# MA-Portenta.net
KiCad netlist of a schematic drawn in Altium Designer
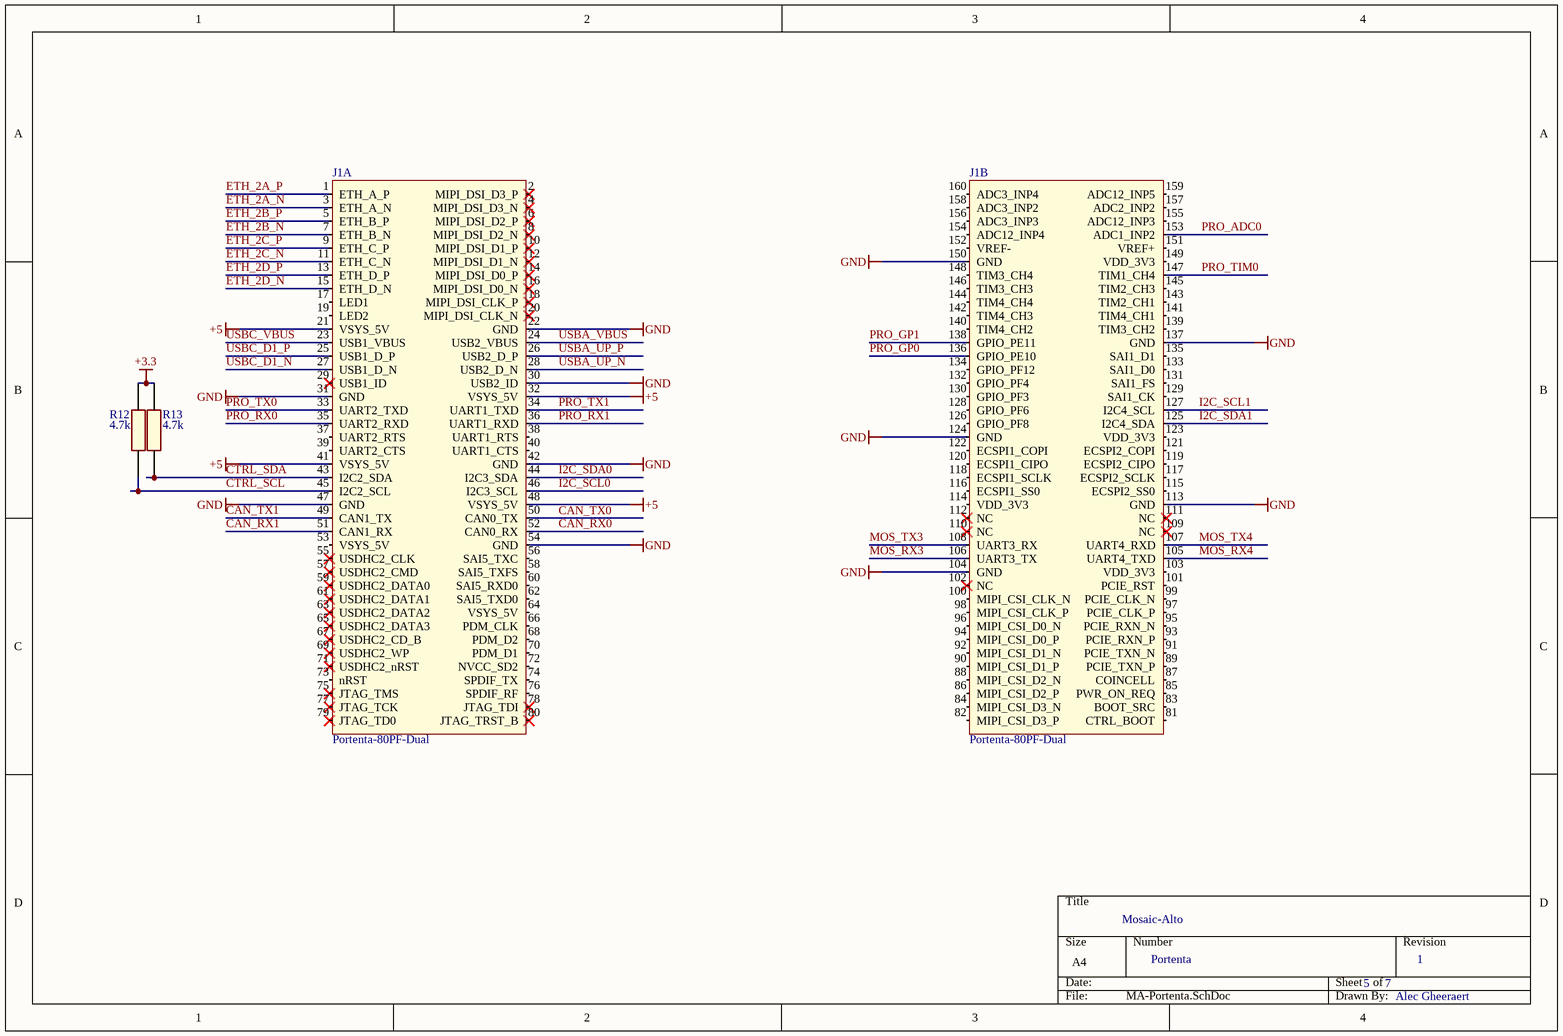
[diagram p0: MA-Portenta.SchDoc]

(export (version "E")
  (design (tool "Eeschema 10.0.6"))
  (components
    (comp (ref "J1")
      (value "Portenta-80PF-Dual")
      (footprint "HRS_DF40C-80DP-0.4V(51)")
      (description "80 Pin Arduino Pro Female")
      (fields (field (name "MANUFACTURER") "Arduino"))
      (libsource (lib "Ghrt") (part "Portenta-80P-Dual"))
    )
    (comp (ref "R12")
      (value "4.7k")
      (footprint "RESC1005X40N")
      (description "0402I 4.7k")
      (fields (field (name "MANUFACTURER") "Walsin") (field (name "TOLERANCE") "1%"))
      (libsource (lib "Ghrt") (part "WR04X4701FTL"))
    )
    (comp (ref "R13")
      (value "4.7k")
      (footprint "RESC1005X40N")
      (description "0402I 4.7k")
      (fields (field (name "MANUFACTURER") "Walsin") (field (name "TOLERANCE") "1%"))
      (libsource (lib "") (part "WR04X4701FTL_1"))
    )
  )
  (nets
    (net (code "1") (name "+3.3") (class "Default")
      (node (ref "R12") (pin "2") (pinfunction "2_2") (pintype "passive"))
      (node (ref "R13") (pin "1") (pinfunction "1_1") (pintype "passive"))
    )
    (net (code "2") (name "+5") (class "Default")
      (node (ref "J1") (pin "21") (pinfunction "VSYS_5V_21") (pintype "passive"))
      (node (ref "J1") (pin "32") (pinfunction "VSYS_5V_32") (pintype "passive"))
      (node (ref "J1") (pin "41") (pinfunction "VSYS_5V_41") (pintype "passive"))
      (node (ref "J1") (pin "48") (pinfunction "VSYS_5V_48") (pintype "passive"))
    )
    (net (code "3") (name "/CAN_RX0") (class "Default")
      (node (ref "J1") (pin "52") (pinfunction "CAN0_RX_52") (pintype "passive"))
    )
    (net (code "4") (name "/CAN_RX1") (class "Default")
      (node (ref "J1") (pin "51") (pinfunction "CAN1_RX_51") (pintype "passive"))
    )
    (net (code "5") (name "/CAN_TX0") (class "Default")
      (node (ref "J1") (pin "50") (pinfunction "CAN0_TX_50") (pintype "passive"))
    )
    (net (code "6") (name "/CAN_TX1") (class "Default")
      (node (ref "J1") (pin "49") (pinfunction "CAN1_TX_49") (pintype "passive"))
    )
    (net (code "7") (name "/CTRL_SCL") (class "Default")
      (node (ref "J1") (pin "45") (pinfunction "I2C2_SCL_45") (pintype "passive"))
      (node (ref "R12") (pin "1") (pinfunction "1_1") (pintype "passive"))
    )
    (net (code "8") (name "/CTRL_SDA") (class "Default")
      (node (ref "J1") (pin "43") (pinfunction "I2C2_SDA_43") (pintype "passive"))
      (node (ref "R13") (pin "2") (pinfunction "2_2") (pintype "passive"))
    )
    (net (code "9") (name "/ETH_2A_N") (class "Default")
      (node (ref "J1") (pin "3") (pinfunction "ETH_A_N_3") (pintype "passive"))
    )
    (net (code "10") (name "/ETH_2A_P") (class "Default")
      (node (ref "J1") (pin "1") (pinfunction "ETH_A_P_1") (pintype "passive"))
    )
    (net (code "11") (name "/ETH_2B_N") (class "Default")
      (node (ref "J1") (pin "7") (pinfunction "ETH_B_N_7") (pintype "passive"))
    )
    (net (code "12") (name "/ETH_2B_P") (class "Default")
      (node (ref "J1") (pin "5") (pinfunction "ETH_B_P_5") (pintype "passive"))
    )
    (net (code "13") (name "/ETH_2C_N") (class "Default")
      (node (ref "J1") (pin "11") (pinfunction "ETH_C_N_11") (pintype "passive"))
    )
    (net (code "14") (name "/ETH_2C_P") (class "Default")
      (node (ref "J1") (pin "9") (pinfunction "ETH_C_P_9") (pintype "passive"))
    )
    (net (code "15") (name "/ETH_2D_N") (class "Default")
      (node (ref "J1") (pin "15") (pinfunction "ETH_D_N_15") (pintype "passive"))
    )
    (net (code "16") (name "/ETH_2D_P") (class "Default")
      (node (ref "J1") (pin "13") (pinfunction "ETH_D_P_13") (pintype "passive"))
    )
    (net (code "17") (name "/I2C_SCL0") (class "Default")
      (node (ref "J1") (pin "46") (pinfunction "I2C3_SCL_46") (pintype "passive"))
    )
    (net (code "18") (name "/I2C_SCL1") (class "Default")
      (node (ref "J1") (pin "127") (pinfunction "I2C4_SCL_127") (pintype "passive"))
    )
    (net (code "19") (name "/I2C_SDA0") (class "Default")
      (node (ref "J1") (pin "44") (pinfunction "I2C3_SDA_44") (pintype "passive"))
    )
    (net (code "20") (name "/I2C_SDA1") (class "Default")
      (node (ref "J1") (pin "125") (pinfunction "I2C4_SDA_125") (pintype "passive"))
    )
    (net (code "21") (name "/MOS_RX3") (class "Default")
      (node (ref "J1") (pin "106") (pinfunction "UART3_TX_106") (pintype "passive"))
    )
    (net (code "22") (name "/MOS_RX4") (class "Default")
      (node (ref "J1") (pin "105") (pinfunction "UART4_TXD_105") (pintype "passive"))
    )
    (net (code "23") (name "/MOS_TX3") (class "Default")
      (node (ref "J1") (pin "108") (pinfunction "UART3_RX_108") (pintype "passive"))
    )
    (net (code "24") (name "/MOS_TX4") (class "Default")
      (node (ref "J1") (pin "107") (pinfunction "UART4_RXD_107") (pintype "passive"))
    )
    (net (code "25") (name "/PRO_ADC0") (class "Default")
      (node (ref "J1") (pin "153") (pinfunction "ADC1_INP2_153") (pintype "passive"))
    )
    (net (code "26") (name "/PRO_GP0") (class "Default")
      (node (ref "J1") (pin "136") (pinfunction "GPIO_PE10_136") (pintype "passive"))
    )
    (net (code "27") (name "/PRO_GP1") (class "Default")
      (node (ref "J1") (pin "138") (pinfunction "GPIO_PE11_138") (pintype "passive"))
    )
    (net (code "28") (name "/PRO_RX0") (class "Default")
      (node (ref "J1") (pin "35") (pinfunction "UART2_RXD_35") (pintype "passive"))
    )
    (net (code "29") (name "/PRO_RX1") (class "Default")
      (node (ref "J1") (pin "36") (pinfunction "UART1_RXD_36") (pintype "passive"))
    )
    (net (code "30") (name "/PRO_TIM0") (class "Default")
      (node (ref "J1") (pin "147") (pinfunction "TIM1_CH4_147") (pintype "passive"))
    )
    (net (code "31") (name "/PRO_TX0") (class "Default")
      (node (ref "J1") (pin "33") (pinfunction "UART2_TXD_33") (pintype "passive"))
    )
    (net (code "32") (name "/PRO_TX1") (class "Default")
      (node (ref "J1") (pin "34") (pinfunction "UART1_TXD_34") (pintype "passive"))
    )
    (net (code "33") (name "/USBA_UP_N") (class "Default")
      (node (ref "J1") (pin "28") (pinfunction "USB2_D_N_28") (pintype "passive"))
    )
    (net (code "34") (name "/USBA_UP_P") (class "Default")
      (node (ref "J1") (pin "26") (pinfunction "USB2_D_P_26") (pintype "passive"))
    )
    (net (code "35") (name "/USBA_VBUS") (class "Default")
      (node (ref "J1") (pin "24") (pinfunction "USB2_VBUS_24") (pintype "passive"))
    )
    (net (code "36") (name "/USBC_D1_N") (class "Default")
      (node (ref "J1") (pin "27") (pinfunction "USB1_D_N_27") (pintype "passive"))
    )
    (net (code "37") (name "/USBC_D1_P") (class "Default")
      (node (ref "J1") (pin "25") (pinfunction "USB1_D_P_25") (pintype "passive"))
    )
    (net (code "38") (name "/USBC_VBUS") (class "Default")
      (node (ref "J1") (pin "23") (pinfunction "USB1_VBUS_23") (pintype "passive"))
    )
    (net (code "39") (name "GND") (class "Default")
      (node (ref "J1") (pin "104") (pinfunction "GND_104") (pintype "passive"))
      (node (ref "J1") (pin "113") (pinfunction "GND_113") (pintype "passive"))
      (node (ref "J1") (pin "124") (pinfunction "GND_124") (pintype "passive"))
      (node (ref "J1") (pin "137") (pinfunction "GND_137") (pintype "passive"))
      (node (ref "J1") (pin "150") (pinfunction "GND_150") (pintype "passive"))
      (node (ref "J1") (pin "22") (pinfunction "GND_22") (pintype "passive"))
      (node (ref "J1") (pin "30") (pinfunction "USB2_ID_30") (pintype "passive"))
      (node (ref "J1") (pin "31") (pinfunction "GND_31") (pintype "passive"))
      (node (ref "J1") (pin "42") (pinfunction "GND_42") (pintype "passive"))
      (node (ref "J1") (pin "47") (pinfunction "GND_47") (pintype "passive"))
      (node (ref "J1") (pin "54") (pinfunction "GND_54") (pintype "passive"))
    )
    (net (code "40") (name "unconnected-(J1A-JTAG_TCK-Pad77)") (class "Default")
      (node (ref "J1") (pin "77") (pinfunction "JTAG_TCK_77") (pintype "passive+no_connect"))
    )
    (net (code "41") (name "unconnected-(J1A-JTAG_TD0-Pad79)") (class "Default")
      (node (ref "J1") (pin "79") (pinfunction "JTAG_TD0_79") (pintype "passive+no_connect"))
    )
    (net (code "42") (name "unconnected-(J1A-JTAG_TDI-Pad78)") (class "Default")
      (node (ref "J1") (pin "78") (pinfunction "JTAG_TDI_78") (pintype "passive+no_connect"))
    )
    (net (code "43") (name "unconnected-(J1A-JTAG_TMS-Pad75)") (class "Default")
      (node (ref "J1") (pin "75") (pinfunction "JTAG_TMS_75") (pintype "passive+no_connect"))
    )
    (net (code "44") (name "unconnected-(J1A-JTAG_TRST_B-Pad80)") (class "Default")
      (node (ref "J1") (pin "80") (pinfunction "JTAG_TRST_B_80") (pintype "passive+no_connect"))
    )
    (net (code "45") (name "unconnected-(J1A-LED1-Pad17)") (class "Default")
      (node (ref "J1") (pin "17") (pinfunction "LED1_17") (pintype "passive"))
    )
    (net (code "46") (name "unconnected-(J1A-LED2-Pad19)") (class "Default")
      (node (ref "J1") (pin "19") (pinfunction "LED2_19") (pintype "passive"))
    )
    (net (code "47") (name "unconnected-(J1A-MIPI_DSI_CLK_N-Pad20)") (class "Default")
      (node (ref "J1") (pin "20") (pinfunction "MIPI_DSI_CLK_N_20") (pintype "passive+no_connect"))
    )
    (net (code "48") (name "unconnected-(J1A-MIPI_DSI_CLK_P-Pad18)") (class "Default")
      (node (ref "J1") (pin "18") (pinfunction "MIPI_DSI_CLK_P_18") (pintype "passive+no_connect"))
    )
    (net (code "49") (name "unconnected-(J1A-MIPI_DSI_D0_N-Pad16)") (class "Default")
      (node (ref "J1") (pin "16") (pinfunction "MIPI_DSI_D0_N_16") (pintype "passive+no_connect"))
    )
    (net (code "50") (name "unconnected-(J1A-MIPI_DSI_D0_P-Pad14)") (class "Default")
      (node (ref "J1") (pin "14") (pinfunction "MIPI_DSI_D0_P_14") (pintype "passive+no_connect"))
    )
    (net (code "51") (name "unconnected-(J1A-MIPI_DSI_D1_N-Pad12)") (class "Default")
      (node (ref "J1") (pin "12") (pinfunction "MIPI_DSI_D1_N_12") (pintype "passive+no_connect"))
    )
    (net (code "52") (name "unconnected-(J1A-MIPI_DSI_D1_P-Pad10)") (class "Default")
      (node (ref "J1") (pin "10") (pinfunction "MIPI_DSI_D1_P_10") (pintype "passive+no_connect"))
    )
    (net (code "53") (name "unconnected-(J1A-MIPI_DSI_D2_N-Pad8)") (class "Default")
      (node (ref "J1") (pin "8") (pinfunction "MIPI_DSI_D2_N_8") (pintype "passive+no_connect"))
    )
    (net (code "54") (name "unconnected-(J1A-MIPI_DSI_D2_P-Pad6)") (class "Default")
      (node (ref "J1") (pin "6") (pinfunction "MIPI_DSI_D2_P_6") (pintype "passive+no_connect"))
    )
    (net (code "55") (name "unconnected-(J1A-MIPI_DSI_D3_N-Pad4)") (class "Default")
      (node (ref "J1") (pin "4") (pinfunction "MIPI_DSI_D3_N_4") (pintype "passive+no_connect"))
    )
    (net (code "56") (name "unconnected-(J1A-MIPI_DSI_D3_P-Pad2)") (class "Default")
      (node (ref "J1") (pin "2") (pinfunction "MIPI_DSI_D3_P_2") (pintype "passive+no_connect"))
    )
    (net (code "57") (name "unconnected-(J1A-NVCC_SD2-Pad72)") (class "Default")
      (node (ref "J1") (pin "72") (pinfunction "NVCC_SD2_72") (pintype "passive"))
    )
    (net (code "58") (name "unconnected-(J1A-PDM_CLK-Pad66)") (class "Default")
      (node (ref "J1") (pin "66") (pinfunction "PDM_CLK_66") (pintype "passive"))
    )
    (net (code "59") (name "unconnected-(J1A-PDM_D1-Pad70)") (class "Default")
      (node (ref "J1") (pin "70") (pinfunction "PDM_D1_70") (pintype "passive"))
    )
    (net (code "60") (name "unconnected-(J1A-PDM_D2-Pad68)") (class "Default")
      (node (ref "J1") (pin "68") (pinfunction "PDM_D2_68") (pintype "passive"))
    )
    (net (code "61") (name "unconnected-(J1A-SAI5_RXD0-Pad60)") (class "Default")
      (node (ref "J1") (pin "60") (pinfunction "SAI5_RXD0_60") (pintype "passive"))
    )
    (net (code "62") (name "unconnected-(J1A-SAI5_TXC-Pad56)") (class "Default")
      (node (ref "J1") (pin "56") (pinfunction "SAI5_TXC_56") (pintype "passive"))
    )
    (net (code "63") (name "unconnected-(J1A-SAI5_TXD0-Pad62)") (class "Default")
      (node (ref "J1") (pin "62") (pinfunction "SAI5_TXD0_62") (pintype "passive"))
    )
    (net (code "64") (name "unconnected-(J1A-SAI5_TXFS-Pad58)") (class "Default")
      (node (ref "J1") (pin "58") (pinfunction "SAI5_TXFS_58") (pintype "passive"))
    )
    (net (code "65") (name "unconnected-(J1A-SPDIF_RF-Pad76)") (class "Default")
      (node (ref "J1") (pin "76") (pinfunction "SPDIF_RF_76") (pintype "passive"))
    )
    (net (code "66") (name "unconnected-(J1A-SPDIF_TX-Pad74)") (class "Default")
      (node (ref "J1") (pin "74") (pinfunction "SPDIF_TX_74") (pintype "passive"))
    )
    (net (code "67") (name "unconnected-(J1A-UART1_CTS-Pad40)") (class "Default")
      (node (ref "J1") (pin "40") (pinfunction "UART1_CTS_40") (pintype "passive"))
    )
    (net (code "68") (name "unconnected-(J1A-UART1_RTS-Pad38)") (class "Default")
      (node (ref "J1") (pin "38") (pinfunction "UART1_RTS_38") (pintype "passive"))
    )
    (net (code "69") (name "unconnected-(J1A-UART2_CTS-Pad39)") (class "Default")
      (node (ref "J1") (pin "39") (pinfunction "UART2_CTS_39") (pintype "passive"))
    )
    (net (code "70") (name "unconnected-(J1A-UART2_RTS-Pad37)") (class "Default")
      (node (ref "J1") (pin "37") (pinfunction "UART2_RTS_37") (pintype "passive"))
    )
    (net (code "71") (name "unconnected-(J1A-USB1_ID-Pad29)") (class "Default")
      (node (ref "J1") (pin "29") (pinfunction "USB1_ID_29") (pintype "passive+no_connect"))
    )
    (net (code "72") (name "unconnected-(J1A-USDHC2_CD_B-Pad67)") (class "Default")
      (node (ref "J1") (pin "67") (pinfunction "USDHC2_CD_B_67") (pintype "passive+no_connect"))
    )
    (net (code "73") (name "unconnected-(J1A-USDHC2_CLK-Pad55)") (class "Default")
      (node (ref "J1") (pin "55") (pinfunction "USDHC2_CLK_55") (pintype "passive+no_connect"))
    )
    (net (code "74") (name "unconnected-(J1A-USDHC2_CMD-Pad57)") (class "Default")
      (node (ref "J1") (pin "57") (pinfunction "USDHC2_CMD_57") (pintype "passive+no_connect"))
    )
    (net (code "75") (name "unconnected-(J1A-USDHC2_DATA0-Pad59)") (class "Default")
      (node (ref "J1") (pin "59") (pinfunction "USDHC2_DATA0_59") (pintype "passive+no_connect"))
    )
    (net (code "76") (name "unconnected-(J1A-USDHC2_DATA1-Pad61)") (class "Default")
      (node (ref "J1") (pin "61") (pinfunction "USDHC2_DATA1_61") (pintype "passive+no_connect"))
    )
    (net (code "77") (name "unconnected-(J1A-USDHC2_DATA2-Pad63)") (class "Default")
      (node (ref "J1") (pin "63") (pinfunction "USDHC2_DATA2_63") (pintype "passive+no_connect"))
    )
    (net (code "78") (name "unconnected-(J1A-USDHC2_DATA3-Pad65)") (class "Default")
      (node (ref "J1") (pin "65") (pinfunction "USDHC2_DATA3_65") (pintype "passive+no_connect"))
    )
    (net (code "79") (name "unconnected-(J1A-USDHC2_WP-Pad69)") (class "Default")
      (node (ref "J1") (pin "69") (pinfunction "USDHC2_WP_69") (pintype "passive+no_connect"))
    )
    (net (code "80") (name "unconnected-(J1A-USDHC2_nRST-Pad71)") (class "Default")
      (node (ref "J1") (pin "71") (pinfunction "USDHC2_nRST_71") (pintype "passive+no_connect"))
    )
    (net (code "81") (name "unconnected-(J1A-VSYS_5V-Pad53)") (class "Default")
      (node (ref "J1") (pin "53") (pinfunction "VSYS_5V_53") (pintype "passive"))
    )
    (net (code "82") (name "unconnected-(J1A-VSYS_5V-Pad64)") (class "Default")
      (node (ref "J1") (pin "64") (pinfunction "VSYS_5V_64") (pintype "passive"))
    )
    (net (code "83") (name "unconnected-(J1A-nRST-Pad73)") (class "Default")
      (node (ref "J1") (pin "73") (pinfunction "nRST_73") (pintype "passive"))
    )
    (net (code "84") (name "unconnected-(J1B-ADC2_INP2-Pad157)") (class "Default")
      (node (ref "J1") (pin "157") (pinfunction "ADC2_INP2_157") (pintype "passive"))
    )
    (net (code "85") (name "unconnected-(J1B-ADC3_INP2-Pad158)") (class "Default")
      (node (ref "J1") (pin "158") (pinfunction "ADC3_INP2_158") (pintype "passive"))
    )
    (net (code "86") (name "unconnected-(J1B-ADC3_INP3-Pad156)") (class "Default")
      (node (ref "J1") (pin "156") (pinfunction "ADC3_INP3_156") (pintype "passive"))
    )
    (net (code "87") (name "unconnected-(J1B-ADC3_INP4-Pad160)") (class "Default")
      (node (ref "J1") (pin "160") (pinfunction "ADC3_INP4_160") (pintype "passive"))
    )
    (net (code "88") (name "unconnected-(J1B-ADC12_INP3-Pad155)") (class "Default")
      (node (ref "J1") (pin "155") (pinfunction "ADC12_INP3_155") (pintype "passive"))
    )
    (net (code "89") (name "unconnected-(J1B-ADC12_INP4-Pad154)") (class "Default")
      (node (ref "J1") (pin "154") (pinfunction "ADC12_INP4_154") (pintype "passive"))
    )
    (net (code "90") (name "unconnected-(J1B-ADC12_INP5-Pad159)") (class "Default")
      (node (ref "J1") (pin "159") (pinfunction "ADC12_INP5_159") (pintype "passive"))
    )
    (net (code "91") (name "unconnected-(J1B-BOOT_SRC-Pad83)") (class "Default")
      (node (ref "J1") (pin "83") (pinfunction "BOOT_SRC_83") (pintype "passive"))
    )
    (net (code "92") (name "unconnected-(J1B-COINCELL-Pad87)") (class "Default")
      (node (ref "J1") (pin "87") (pinfunction "COINCELL_87") (pintype "passive"))
    )
    (net (code "93") (name "unconnected-(J1B-CTRL_BOOT-Pad81)") (class "Default")
      (node (ref "J1") (pin "81") (pinfunction "CTRL_BOOT_81") (pintype "passive"))
    )
    (net (code "94") (name "unconnected-(J1B-ECSPI1_CIPO-Pad120)") (class "Default")
      (node (ref "J1") (pin "120") (pinfunction "ECSPI1_CIPO_120") (pintype "passive"))
    )
    (net (code "95") (name "unconnected-(J1B-ECSPI1_COPI-Pad122)") (class "Default")
      (node (ref "J1") (pin "122") (pinfunction "ECSPI1_COPI_122") (pintype "passive"))
    )
    (net (code "96") (name "unconnected-(J1B-ECSPI1_SCLK-Pad118)") (class "Default")
      (node (ref "J1") (pin "118") (pinfunction "ECSPI1_SCLK_118") (pintype "passive"))
    )
    (net (code "97") (name "unconnected-(J1B-ECSPI1_SS0-Pad116)") (class "Default")
      (node (ref "J1") (pin "116") (pinfunction "ECSPI1_SS0_116") (pintype "passive"))
    )
    (net (code "98") (name "unconnected-(J1B-ECSPI2_CIPO-Pad119)") (class "Default")
      (node (ref "J1") (pin "119") (pinfunction "ECSPI2_CIPO_119") (pintype "passive"))
    )
    (net (code "99") (name "unconnected-(J1B-ECSPI2_COPI-Pad121)") (class "Default")
      (node (ref "J1") (pin "121") (pinfunction "ECSPI2_COPI_121") (pintype "passive"))
    )
    (net (code "100") (name "unconnected-(J1B-ECSPI2_SCLK-Pad117)") (class "Default")
      (node (ref "J1") (pin "117") (pinfunction "ECSPI2_SCLK_117") (pintype "passive"))
    )
    (net (code "101") (name "unconnected-(J1B-ECSPI2_SS0-Pad115)") (class "Default")
      (node (ref "J1") (pin "115") (pinfunction "ECSPI2_SS0_115") (pintype "passive"))
    )
    (net (code "102") (name "unconnected-(J1B-GPIO_PF3-Pad130)") (class "Default")
      (node (ref "J1") (pin "130") (pinfunction "GPIO_PF3_130") (pintype "passive"))
    )
    (net (code "103") (name "unconnected-(J1B-GPIO_PF4-Pad132)") (class "Default")
      (node (ref "J1") (pin "132") (pinfunction "GPIO_PF4_132") (pintype "passive"))
    )
    (net (code "104") (name "unconnected-(J1B-GPIO_PF6-Pad128)") (class "Default")
      (node (ref "J1") (pin "128") (pinfunction "GPIO_PF6_128") (pintype "passive"))
    )
    (net (code "105") (name "unconnected-(J1B-GPIO_PF8-Pad126)") (class "Default")
      (node (ref "J1") (pin "126") (pinfunction "GPIO_PF8_126") (pintype "passive"))
    )
    (net (code "106") (name "unconnected-(J1B-GPIO_PF12-Pad134)") (class "Default")
      (node (ref "J1") (pin "134") (pinfunction "GPIO_PF12_134") (pintype "passive"))
    )
    (net (code "107") (name "unconnected-(J1B-MIPI_CSI_CLK_N-Pad100)") (class "Default")
      (node (ref "J1") (pin "100") (pinfunction "MIPI_CSI_CLK_N_100") (pintype "passive"))
    )
    (net (code "108") (name "unconnected-(J1B-MIPI_CSI_CLK_P-Pad98)") (class "Default")
      (node (ref "J1") (pin "98") (pinfunction "MIPI_CSI_CLK_P_98") (pintype "passive"))
    )
    (net (code "109") (name "unconnected-(J1B-MIPI_CSI_D0_N-Pad96)") (class "Default")
      (node (ref "J1") (pin "96") (pinfunction "MIPI_CSI_D0_N_96") (pintype "passive"))
    )
    (net (code "110") (name "unconnected-(J1B-MIPI_CSI_D0_P-Pad94)") (class "Default")
      (node (ref "J1") (pin "94") (pinfunction "MIPI_CSI_D0_P_94") (pintype "passive"))
    )
    (net (code "111") (name "unconnected-(J1B-MIPI_CSI_D1_N-Pad92)") (class "Default")
      (node (ref "J1") (pin "92") (pinfunction "MIPI_CSI_D1_N_92") (pintype "passive"))
    )
    (net (code "112") (name "unconnected-(J1B-MIPI_CSI_D1_P-Pad90)") (class "Default")
      (node (ref "J1") (pin "90") (pinfunction "MIPI_CSI_D1_P_90") (pintype "passive"))
    )
    (net (code "113") (name "unconnected-(J1B-MIPI_CSI_D2_N-Pad88)") (class "Default")
      (node (ref "J1") (pin "88") (pinfunction "MIPI_CSI_D2_N_88") (pintype "passive"))
    )
    (net (code "114") (name "unconnected-(J1B-MIPI_CSI_D2_P-Pad86)") (class "Default")
      (node (ref "J1") (pin "86") (pinfunction "MIPI_CSI_D2_P_86") (pintype "passive"))
    )
    (net (code "115") (name "unconnected-(J1B-MIPI_CSI_D3_N-Pad84)") (class "Default")
      (node (ref "J1") (pin "84") (pinfunction "MIPI_CSI_D3_N_84") (pintype "passive"))
    )
    (net (code "116") (name "unconnected-(J1B-MIPI_CSI_D3_P-Pad82)") (class "Default")
      (node (ref "J1") (pin "82") (pinfunction "MIPI_CSI_D3_P_82") (pintype "passive"))
    )
    (net (code "117") (name "unconnected-(J1B-NC-Pad102)") (class "Default")
      (node (ref "J1") (pin "102") (pinfunction "NC_102") (pintype "passive+no_connect"))
    )
    (net (code "118") (name "unconnected-(J1B-NC-Pad109)") (class "Default")
      (node (ref "J1") (pin "109") (pinfunction "NC_109") (pintype "passive+no_connect"))
    )
    (net (code "119") (name "unconnected-(J1B-NC-Pad110)") (class "Default")
      (node (ref "J1") (pin "110") (pinfunction "NC_110") (pintype "passive+no_connect"))
    )
    (net (code "120") (name "unconnected-(J1B-NC-Pad111)") (class "Default")
      (node (ref "J1") (pin "111") (pinfunction "NC_111") (pintype "passive+no_connect"))
    )
    (net (code "121") (name "unconnected-(J1B-NC-Pad112)") (class "Default")
      (node (ref "J1") (pin "112") (pinfunction "NC_112") (pintype "passive+no_connect"))
    )
    (net (code "122") (name "unconnected-(J1B-PCIE_CLK_N-Pad99)") (class "Default")
      (node (ref "J1") (pin "99") (pinfunction "PCIE_CLK_N_99") (pintype "passive"))
    )
    (net (code "123") (name "unconnected-(J1B-PCIE_CLK_P-Pad97)") (class "Default")
      (node (ref "J1") (pin "97") (pinfunction "PCIE_CLK_P_97") (pintype "passive"))
    )
    (net (code "124") (name "unconnected-(J1B-PCIE_RST-Pad101)") (class "Default")
      (node (ref "J1") (pin "101") (pinfunction "PCIE_RST_101") (pintype "passive"))
    )
    (net (code "125") (name "unconnected-(J1B-PCIE_RXN_N-Pad95)") (class "Default")
      (node (ref "J1") (pin "95") (pinfunction "PCIE_RXN_N_95") (pintype "passive"))
    )
    (net (code "126") (name "unconnected-(J1B-PCIE_RXN_P-Pad93)") (class "Default")
      (node (ref "J1") (pin "93") (pinfunction "PCIE_RXN_P_93") (pintype "passive"))
    )
    (net (code "127") (name "unconnected-(J1B-PCIE_TXN_N-Pad91)") (class "Default")
      (node (ref "J1") (pin "91") (pinfunction "PCIE_TXN_N_91") (pintype "passive"))
    )
    (net (code "128") (name "unconnected-(J1B-PCIE_TXN_P-Pad89)") (class "Default")
      (node (ref "J1") (pin "89") (pinfunction "PCIE_TXN_P_89") (pintype "passive"))
    )
    (net (code "129") (name "unconnected-(J1B-PWR_ON_REQ-Pad85)") (class "Default")
      (node (ref "J1") (pin "85") (pinfunction "PWR_ON_REQ_85") (pintype "passive"))
    )
    (net (code "130") (name "unconnected-(J1B-SAI1_CK-Pad129)") (class "Default")
      (node (ref "J1") (pin "129") (pinfunction "SAI1_CK_129") (pintype "passive"))
    )
    (net (code "131") (name "unconnected-(J1B-SAI1_D0-Pad133)") (class "Default")
      (node (ref "J1") (pin "133") (pinfunction "SAI1_D0_133") (pintype "passive"))
    )
    (net (code "132") (name "unconnected-(J1B-SAI1_D1-Pad135)") (class "Default")
      (node (ref "J1") (pin "135") (pinfunction "SAI1_D1_135") (pintype "passive"))
    )
    (net (code "133") (name "unconnected-(J1B-SAI1_FS-Pad131)") (class "Default")
      (node (ref "J1") (pin "131") (pinfunction "SAI1_FS_131") (pintype "passive"))
    )
    (net (code "134") (name "unconnected-(J1B-TIM2_CH1-Pad143)") (class "Default")
      (node (ref "J1") (pin "143") (pinfunction "TIM2_CH1_143") (pintype "passive"))
    )
    (net (code "135") (name "unconnected-(J1B-TIM2_CH3-Pad145)") (class "Default")
      (node (ref "J1") (pin "145") (pinfunction "TIM2_CH3_145") (pintype "passive"))
    )
    (net (code "136") (name "unconnected-(J1B-TIM3_CH2-Pad139)") (class "Default")
      (node (ref "J1") (pin "139") (pinfunction "TIM3_CH2_139") (pintype "passive"))
    )
    (net (code "137") (name "unconnected-(J1B-TIM3_CH3-Pad146)") (class "Default")
      (node (ref "J1") (pin "146") (pinfunction "TIM3_CH3_146") (pintype "passive"))
    )
    (net (code "138") (name "unconnected-(J1B-TIM3_CH4-Pad148)") (class "Default")
      (node (ref "J1") (pin "148") (pinfunction "TIM3_CH4_148") (pintype "passive"))
    )
    (net (code "139") (name "unconnected-(J1B-TIM4_CH1-Pad141)") (class "Default")
      (node (ref "J1") (pin "141") (pinfunction "TIM4_CH1_141") (pintype "passive"))
    )
    (net (code "140") (name "unconnected-(J1B-TIM4_CH2-Pad140)") (class "Default")
      (node (ref "J1") (pin "140") (pinfunction "TIM4_CH2_140") (pintype "passive"))
    )
    (net (code "141") (name "unconnected-(J1B-TIM4_CH3-Pad142)") (class "Default")
      (node (ref "J1") (pin "142") (pinfunction "TIM4_CH3_142") (pintype "passive"))
    )
    (net (code "142") (name "unconnected-(J1B-TIM4_CH4-Pad144)") (class "Default")
      (node (ref "J1") (pin "144") (pinfunction "TIM4_CH4_144") (pintype "passive"))
    )
    (net (code "143") (name "unconnected-(J1B-VDD_3V3-Pad103)") (class "Default")
      (node (ref "J1") (pin "103") (pinfunction "VDD_3V3_103") (pintype "passive"))
    )
    (net (code "144") (name "unconnected-(J1B-VDD_3V3-Pad114)") (class "Default")
      (node (ref "J1") (pin "114") (pinfunction "VDD_3V3_114") (pintype "passive"))
    )
    (net (code "145") (name "unconnected-(J1B-VDD_3V3-Pad123)") (class "Default")
      (node (ref "J1") (pin "123") (pinfunction "VDD_3V3_123") (pintype "passive"))
    )
    (net (code "146") (name "unconnected-(J1B-VDD_3V3-Pad149)") (class "Default")
      (node (ref "J1") (pin "149") (pinfunction "VDD_3V3_149") (pintype "passive"))
    )
    (net (code "147") (name "unconnected-(J1B-VREF+-Pad151)") (class "Default")
      (node (ref "J1") (pin "151") (pinfunction "VREF+_151") (pintype "passive"))
    )
    (net (code "148") (name "unconnected-(J1B-VREF--Pad152)") (class "Default")
      (node (ref "J1") (pin "152") (pinfunction "VREF-_152") (pintype "passive"))
    )
  )
)
